# MS1050_EVB_V2_0.net
KiCad netlist of a schematic drawn in Altium Designer
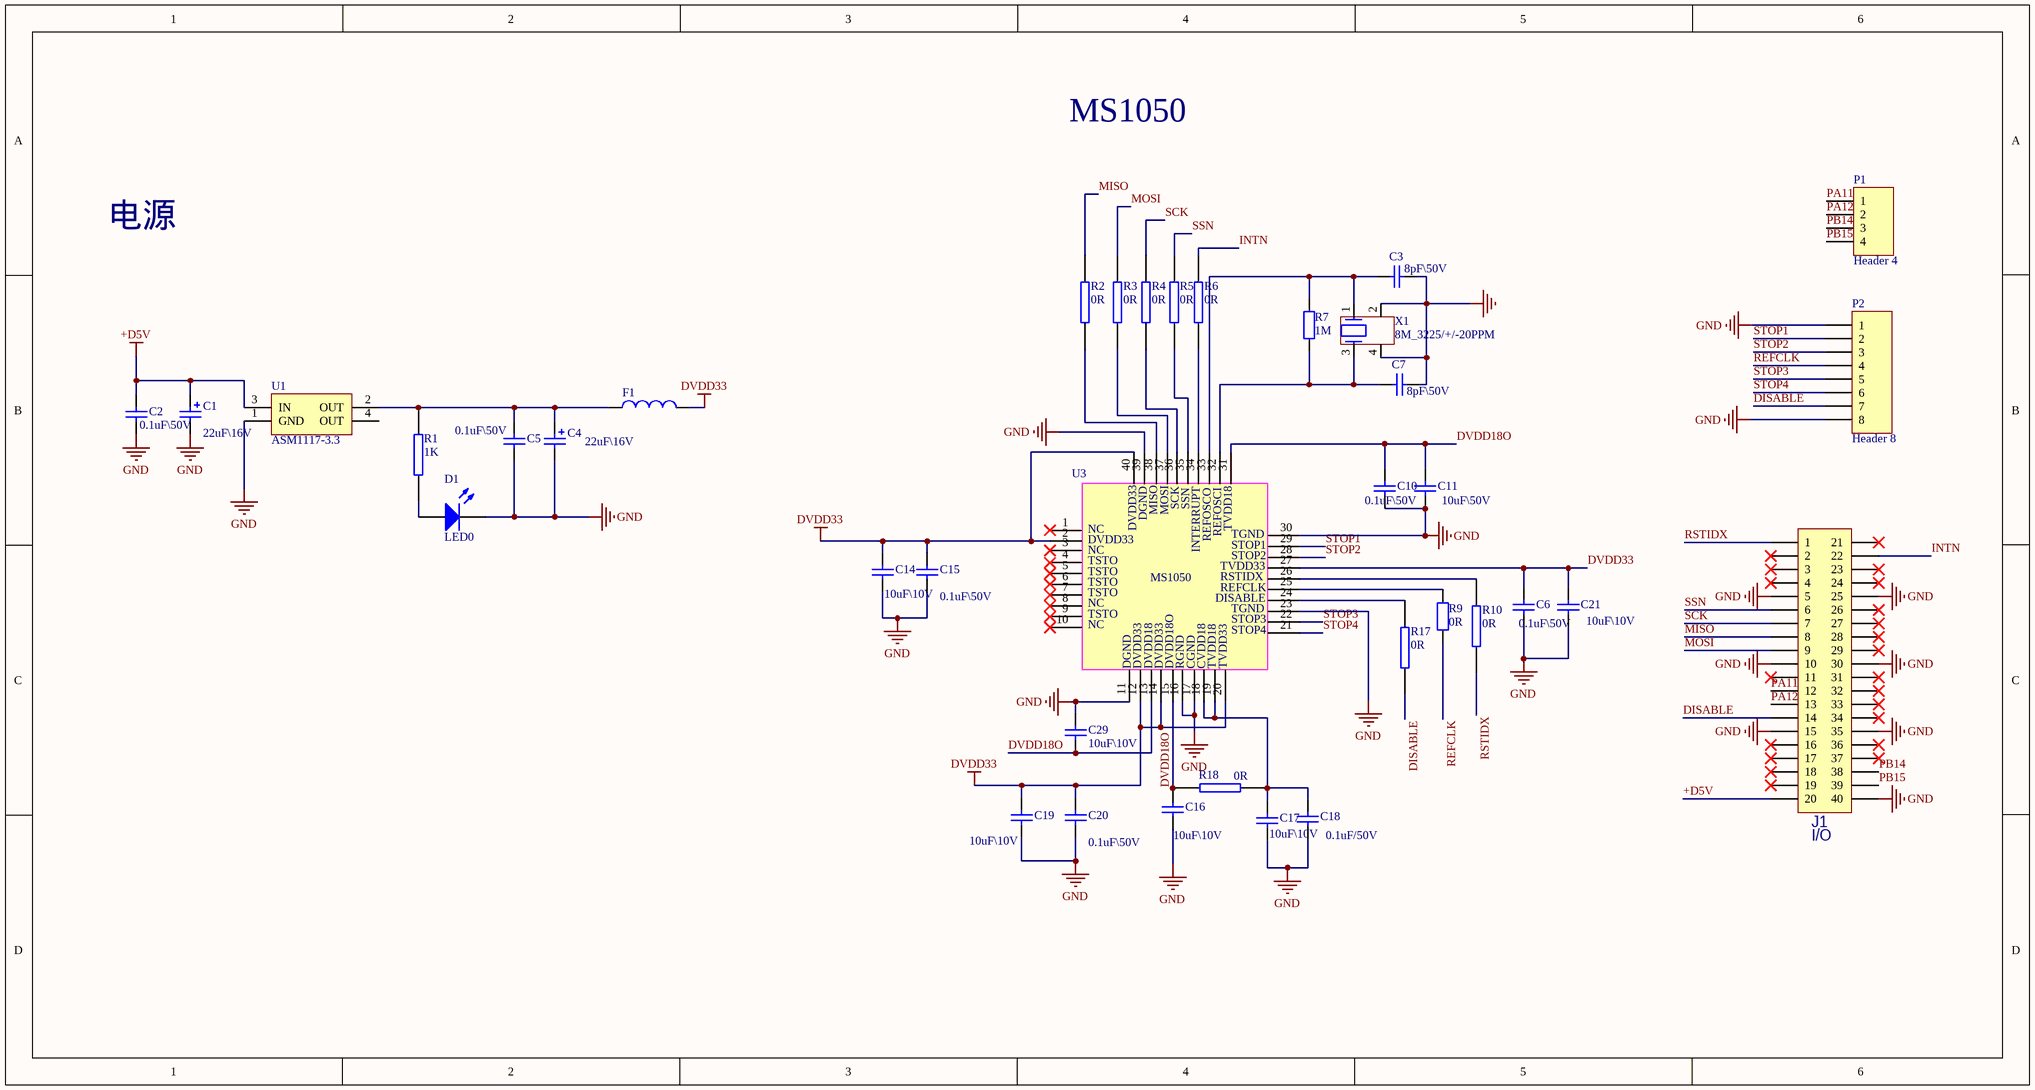
[diagram p0: MS1050_EVB_V2.0.SchDoc]

(export (version "E")
  (design (tool "Eeschema 10.0.6"))
  (components
    (comp (ref "C1")
      (value "22u~{F}16V")
      (footprint "3216")
      (description "Cap，22uF，20%，3216")
      (fields (field (name "Comment") "22uF") (field (name "PUBLISHER") "Altium Limited"))
      (libsource (lib "Miscellaneous Devices") (part "Cap Pol2"))
    )
    (comp (ref "C2")
      (value "0.1u~{F}50V")
      (footprint "0603C")
      (description "Cap，0.1 uF，1%，0603")
      (fields (field (name "Comment") "0.1uF") (field (name "PUBLISHER") "Altium Limited"))
      (libsource (lib "Miscellaneous Devices") (part "Cap"))
    )
    (comp (ref "C3")
      (value "8p~{F}50V")
      (footprint "0603C")
      (description "Cap，8pF，1%，0603")
      (fields (field (name "Comment") "8pF") (field (name "PUBLISHER") "Altium Limited"))
      (libsource (lib "Miscellaneous Devices") (part "Cap"))
    )
    (comp (ref "C4")
      (value "22u~{F}16V")
      (footprint "3216")
      (description "Cap，22uF，20%，3216")
      (fields (field (name "Comment") "22uF") (field (name "PUBLISHER") "Altium Limited"))
      (libsource (lib "Miscellaneous Devices") (part "Cap Pol2"))
    )
    (comp (ref "C5")
      (value "0.1u~{F}50V")
      (footprint "0603c")
      (description "Cap，0.1uF，1%，0603")
      (fields (field (name "Comment") "0.1uF") (field (name "PUBLISHER") "Altium Limited"))
      (libsource (lib "Miscellaneous Devices") (part "Cap"))
    )
    (comp (ref "C6")
      (value "0.1u~{F}50V")
      (footprint "0603c")
      (description "Cap，0.1uF，1%，0603")
      (fields (field (name "Comment") "0.1uF") (field (name "PUBLISHER") "Altium Limited"))
      (libsource (lib "MS1050_Demo") (part "Cap"))
    )
    (comp (ref "C7")
      (value "8p~{F}50V")
      (footprint "0603C")
      (description "Cap，8pF，1%，0603")
      (fields (field (name "Comment") "8pF") (field (name "PUBLISHER") "Altium Limited"))
      (libsource (lib "Miscellaneous Devices") (part "Cap"))
    )
    (comp (ref "C10")
      (value "0.1u~{F}50V")
      (footprint "0603c")
      (description "Cap，0.1uF，1%，0603")
      (fields (field (name "Comment") "0.1uF") (field (name "PUBLISHER") "Altium Limited"))
      (libsource (lib "MS1050_Demo") (part "Cap"))
    )
    (comp (ref "C11")
      (value "10u~{F}50V")
      (footprint "0603c")
      (description "Cap，10 uF，1%，0603")
      (fields (field (name "Comment") "10uF") (field (name "PUBLISHER") "Altium Limited"))
      (libsource (lib "MS1050_Demo") (part "Cap"))
    )
    (comp (ref "C14")
      (value "10u~{F}10V")
      (footprint "0603c")
      (description "Cap，10 uF，1%，0603")
      (fields (field (name "Comment") "10uF") (field (name "PUBLISHER") "Altium Limited"))
      (libsource (lib "MS1050_Demo") (part "Cap"))
    )
    (comp (ref "C15")
      (value "0.1u~{F}50V")
      (footprint "0603c")
      (description "Cap，0.1uF，1%，0603")
      (fields (field (name "Comment") "0.1uF") (field (name "PUBLISHER") "Altium Limited"))
      (libsource (lib "MS1050_Demo") (part "Cap"))
    )
    (comp (ref "C16")
      (value "10u~{F}10V")
      (footprint "0603c")
      (description "Cap，10 uF，1%，0603")
      (fields (field (name "Comment") "10uF") (field (name "PUBLISHER") "Altium Limited"))
      (libsource (lib "MS1050_Demo") (part "Cap"))
    )
    (comp (ref "C17")
      (value "10u~{F}10V")
      (footprint "0603c")
      (description "Cap，10 uF，1%，0603")
      (fields (field (name "Comment") "10uF") (field (name "PUBLISHER") "Altium Limited"))
      (libsource (lib "MS1050_Demo") (part "Cap"))
    )
    (comp (ref "C18")
      (value "0.1uF/50V")
      (footprint "0603c")
      (description "Cap，0.1uF，1%，0603")
      (fields (field (name "Comment") "0.1uF") (field (name "PUBLISHER") "Altium Limited"))
      (libsource (lib "MS1050_Demo") (part "Cap"))
    )
    (comp (ref "C19")
      (value "10u~{F}10V")
      (footprint "0603c")
      (description "Cap，10 uF，1%，0603")
      (fields (field (name "Comment") "10uF") (field (name "PUBLISHER") "Altium Limited"))
      (libsource (lib "MS1050_Demo") (part "Cap"))
    )
    (comp (ref "C20")
      (value "0.1u~{F}50V")
      (footprint "0603c")
      (description "Cap，0.1uF，1%，0603")
      (fields (field (name "Comment") "0.1uF") (field (name "PUBLISHER") "Altium Limited"))
      (libsource (lib "MS1050_Demo") (part "Cap"))
    )
    (comp (ref "C21")
      (value "10u~{F}10V")
      (footprint "0603c")
      (description "Cap，10 uF，1%，0603")
      (fields (field (name "Comment") "10uF") (field (name "PUBLISHER") "Altium Limited"))
      (libsource (lib "MS1050_Demo") (part "Cap"))
    )
    (comp (ref "C29")
      (value "10u~{F}10V")
      (footprint "0603c")
      (description "Cap，10 uF，1%，0603")
      (fields (field (name "Comment") "10uF") (field (name "PUBLISHER") "Altium Limited"))
      (libsource (lib "MS1050_Demo") (part "Cap"))
    )
    (comp (ref "D1")
      (value "LED0")
      (footprint "LED 0603R")
      (description "Green LED")
      (fields (field (name "PUBLISHER") "Altium Limited"))
      (libsource (lib "Miscellaneous Devices") (part "LED0"))
    )
    (comp (ref "F1")
      (value "~")
      (footprint "R0603")
      (description "Inductor")
      (fields (field (name "PUBLISHER") "Altium Limited"))
      (libsource (lib "Miscellaneous Devices") (part "Inductor"))
    )
    (comp (ref "J1")
      (value "I/O")
      (footprint "SIP20x2B")
      (description "Header, 40-Pin, Dual row")
      (fields (field (name "PUBLISHER") "*"))
      (libsource (lib "My_Schlib") (part "Header 20X2A"))
    )
    (comp (ref "P1")
      (value "Header 4")
      (footprint "HDR1X4")
      (description "Header, 4-Pin")
      (fields (field (name "PUBLISHER") "Altium Limited"))
      (libsource (lib "MS1050_Demo") (part "Header 4"))
    )
    (comp (ref "P2")
      (value "Header 8")
      (footprint "HDR1X8")
      (description "Header, 8-Pin")
      (fields (field (name "PUBLISHER") "Altium Limited"))
      (libsource (lib "Miscellaneous Connectors") (part "Header 8"))
    )
    (comp (ref "R1")
      (value "1K")
      (footprint "R0603")
      (description "RES，1.00K ohm，1%，0.125W，0603")
      (libsource (lib "*") (part "RES2"))
    )
    (comp (ref "R2")
      (value "0R")
      (footprint "R0603")
      (description "RES，0 ohm，1%，0.125W，0603")
      (libsource (lib "MS1050_Demo") (part "RES2_1"))
    )
    (comp (ref "R3")
      (value "0R")
      (footprint "R0603")
      (description "RES，0 ohm，1%，0.125W，0603")
      (libsource (lib "MS1050_Demo") (part "RES2_1"))
    )
    (comp (ref "R4")
      (value "0R")
      (footprint "R0603")
      (description "RES，0 ohm，1%，0.125W，0603")
      (libsource (lib "MS1050_Demo") (part "RES2_1"))
    )
    (comp (ref "R5")
      (value "0R")
      (footprint "R0603")
      (description "RES，0 ohm，1%，0.125W，0603")
      (libsource (lib "MS1050_Demo") (part "RES2_1"))
    )
    (comp (ref "R6")
      (value "0R")
      (footprint "R0603")
      (description "RES，0 ohm，1%，0.125W，0603")
      (libsource (lib "MS1050_Demo") (part "RES2_1"))
    )
    (comp (ref "R7")
      (value "1M")
      (footprint "R0603")
      (description "RES，1M ohm，1%，0.125W，0603")
      (fields (field (name "PUBLISHER") "Altium Limited"))
      (libsource (lib "Miscellaneous Devices") (part "Res2"))
    )
    (comp (ref "R9")
      (value "0R")
      (footprint "R0603")
      (description "Resistor")
      (fields (field (name "Comment") "Res2") (field (name "PUBLISHER") "Altium Limited"))
      (libsource (lib "MS1050_Demo") (part "Res2_3"))
    )
    (comp (ref "R10")
      (value "0R")
      (footprint "R0603")
      (description "RES，0 ohm，1%，0.125W，0603")
      (libsource (lib "MS1050_Demo") (part "RES2_1"))
    )
    (comp (ref "R17")
      (value "0R")
      (footprint "R0603")
      (description "RES，0 ohm，1%，0.125W，0603")
      (libsource (lib "MS1050_Demo") (part "RES2_1"))
    )
    (comp (ref "R18")
      (value "0R")
      (footprint "R0603")
      (description "RES，0 ohm，1%，0.125W，0603")
      (libsource (lib "MS1050_Demo") (part "RES2_1"))
    )
    (comp (ref "U1")
      (value "ASM1117-3.3")
      (footprint "1117")
      (description "800mA and 1A Low Dropout Positive Regulator 2.85V, 3.3V, 5V, and Adjustable")
      (fields (field (name "PUBLISHER") "Altium Limited"))
      (libsource (lib "*") (part "REG1117-3.3"))
    )
    (comp (ref "U3")
      (value "MS1050")
      (footprint "QFN40 6X6_L")
      (libsource (lib "MS1050_Demo") (part "MS1050"))
    )
    (comp (ref "X1")
      (value "8M_3225/+/-20PPM")
      (footprint "OSC 4025-4P")
      (description "SMD3225, 8MHz, 12pF 10%")
      (fields (field (name "MANUFACTURER") "SJK") (field (name "PARTNUMBER") "7U08000E12UCG"))
      (libsource (lib "schlib") (part "XTAL_4_PINS"))
    )
  )
  (nets
    (net (code "1") (name "+D5V") (class "Default")
      (node (ref "C1") (pin "1") (pinfunction "1_1") (pintype "passive"))
      (node (ref "C2") (pin "2") (pinfunction "2_2") (pintype "passive"))
      (node (ref "J1") (pin "20") (pinfunction "20_20") (pintype "passive"))
      (node (ref "U1") (pin "3") (pinfunction "IN_3") (pintype "power_in"))
    )
    (net (code "2") (name "/DISABLE") (class "Default")
      (node (ref "J1") (pin "14") (pinfunction "14_14") (pintype "passive"))
      (node (ref "P2") (pin "7") (pinfunction "7_7") (pintype "passive"))
      (node (ref "R17") (pin "2") (pinfunction "2_2") (pintype "passive"))
    )
    (net (code "3") (name "/DVDD18O") (class "Default")
      (node (ref "C10") (pin "2") (pinfunction "2_2") (pintype "passive"))
      (node (ref "C11") (pin "1") (pinfunction "1_1") (pintype "passive"))
      (node (ref "C16") (pin "2") (pinfunction "2_2") (pintype "passive"))
      (node (ref "C29") (pin "1") (pinfunction "1_1") (pintype "passive"))
      (node (ref "R18") (pin "1") (pinfunction "1_1") (pintype "passive"))
      (node (ref "U3") (pin "13") (pinfunction "13_13") (pintype "passive"))
      (node (ref "U3") (pin "15") (pinfunction "15_15") (pintype "passive"))
      (node (ref "U3") (pin "31") (pinfunction "31_31") (pintype "passive"))
    )
    (net (code "4") (name "/INTN") (class "Default")
      (node (ref "J1") (pin "22") (pinfunction "22_22") (pintype "passive"))
      (node (ref "R6") (pin "2") (pinfunction "2_2") (pintype "passive"))
    )
    (net (code "5") (name "/MISO") (class "Default")
      (node (ref "J1") (pin "8") (pinfunction "8_8") (pintype "passive"))
      (node (ref "R2") (pin "2") (pinfunction "2_2") (pintype "passive"))
    )
    (net (code "6") (name "/MOSI") (class "Default")
      (node (ref "J1") (pin "9") (pinfunction "9_9") (pintype "passive"))
      (node (ref "R3") (pin "2") (pinfunction "2_2") (pintype "passive"))
    )
    (net (code "7") (name "/PA11") (class "Default")
      (node (ref "J1") (pin "12") (pinfunction "12_12") (pintype "passive"))
      (node (ref "P1") (pin "1") (pinfunction "1_1") (pintype "passive"))
    )
    (net (code "8") (name "/PA12") (class "Default")
      (node (ref "J1") (pin "13") (pinfunction "13_13") (pintype "passive"))
      (node (ref "P1") (pin "2") (pinfunction "2_2") (pintype "passive"))
    )
    (net (code "9") (name "/PB14") (class "Default")
      (node (ref "J1") (pin "38") (pinfunction "38_38") (pintype "passive"))
      (node (ref "P1") (pin "3") (pinfunction "3_3") (pintype "passive"))
    )
    (net (code "10") (name "/PB15") (class "Default")
      (node (ref "J1") (pin "39") (pinfunction "39_39") (pintype "passive"))
      (node (ref "P1") (pin "4") (pinfunction "4_4") (pintype "passive"))
    )
    (net (code "11") (name "/REFCLK") (class "Default")
      (node (ref "P2") (pin "4") (pinfunction "4_4") (pintype "passive"))
      (node (ref "R9") (pin "1") (pinfunction "1_1") (pintype "passive"))
    )
    (net (code "12") (name "/RSTIDX") (class "Default")
      (node (ref "J1") (pin "1") (pinfunction "1_1") (pintype "passive"))
      (node (ref "R10") (pin "2") (pinfunction "2_2") (pintype "passive"))
    )
    (net (code "13") (name "/SCK") (class "Default")
      (node (ref "J1") (pin "7") (pinfunction "7_7") (pintype "passive"))
      (node (ref "R4") (pin "2") (pinfunction "2_2") (pintype "passive"))
    )
    (net (code "14") (name "/SSN") (class "Default")
      (node (ref "J1") (pin "6") (pinfunction "6_6") (pintype "passive"))
      (node (ref "R5") (pin "2") (pinfunction "2_2") (pintype "passive"))
    )
    (net (code "15") (name "/STOP1") (class "Default")
      (node (ref "P2") (pin "2") (pinfunction "2_2") (pintype "passive"))
      (node (ref "U3") (pin "29") (pinfunction "29_29") (pintype "passive"))
    )
    (net (code "16") (name "/STOP2") (class "Default")
      (node (ref "P2") (pin "3") (pinfunction "3_3") (pintype "passive"))
      (node (ref "U3") (pin "28") (pinfunction "28_28") (pintype "passive"))
    )
    (net (code "17") (name "/STOP3") (class "Default")
      (node (ref "P2") (pin "5") (pinfunction "5_5") (pintype "passive"))
      (node (ref "U3") (pin "22") (pinfunction "22_22") (pintype "passive"))
    )
    (net (code "18") (name "/STOP4") (class "Default")
      (node (ref "P2") (pin "6") (pinfunction "6_6") (pintype "passive"))
      (node (ref "U3") (pin "21") (pinfunction "21_21") (pintype "passive"))
    )
    (net (code "19") (name "DVDD33") (class "Default")
      (node (ref "C14") (pin "2") (pinfunction "2_2") (pintype "passive"))
      (node (ref "C15") (pin "2") (pinfunction "2_2") (pintype "passive"))
      (node (ref "C19") (pin "2") (pinfunction "2_2") (pintype "passive"))
      (node (ref "C20") (pin "2") (pinfunction "2_2") (pintype "passive"))
      (node (ref "C21") (pin "1") (pinfunction "1_1") (pintype "passive"))
      (node (ref "C6") (pin "1") (pinfunction "1_1") (pintype "passive"))
      (node (ref "F1") (pin "2") (pinfunction "2_2") (pintype "passive"))
      (node (ref "U3") (pin "12") (pinfunction "12_12") (pintype "passive"))
      (node (ref "U3") (pin "14") (pinfunction "14_14") (pintype "passive"))
      (node (ref "U3") (pin "2") (pinfunction "2_2") (pintype "passive"))
      (node (ref "U3") (pin "20") (pinfunction "20_20") (pintype "passive"))
      (node (ref "U3") (pin "27") (pinfunction "27_27") (pintype "passive"))
      (node (ref "U3") (pin "40") (pinfunction "40_40") (pintype "passive"))
    )
    (net (code "20") (name "GND") (class "Default")
      (node (ref "C1") (pin "2") (pinfunction "2_2") (pintype "passive"))
      (node (ref "C10") (pin "1") (pinfunction "1_1") (pintype "passive"))
      (node (ref "C11") (pin "2") (pinfunction "2_2") (pintype "passive"))
      (node (ref "C14") (pin "1") (pinfunction "1_1") (pintype "passive"))
      (node (ref "C15") (pin "1") (pinfunction "1_1") (pintype "passive"))
      (node (ref "C16") (pin "1") (pinfunction "1_1") (pintype "passive"))
      (node (ref "C17") (pin "1") (pinfunction "1_1") (pintype "passive"))
      (node (ref "C18") (pin "1") (pinfunction "1_1") (pintype "passive"))
      (node (ref "C19") (pin "1") (pinfunction "1_1") (pintype "passive"))
      (node (ref "C2") (pin "1") (pinfunction "1_1") (pintype "passive"))
      (node (ref "C20") (pin "1") (pinfunction "1_1") (pintype "passive"))
      (node (ref "C21") (pin "2") (pinfunction "2_2") (pintype "passive"))
      (node (ref "C29") (pin "2") (pinfunction "2_2") (pintype "passive"))
      (node (ref "C3") (pin "2") (pinfunction "2_2") (pintype "passive"))
      (node (ref "C4") (pin "2") (pinfunction "2_2") (pintype "passive"))
      (node (ref "C5") (pin "1") (pinfunction "1_1") (pintype "passive"))
      (node (ref "C6") (pin "2") (pinfunction "2_2") (pintype "passive"))
      (node (ref "C7") (pin "2") (pinfunction "2_2") (pintype "passive"))
      (node (ref "D1") (pin "2") (pinfunction "K_2") (pintype "passive"))
      (node (ref "J1") (pin "10") (pinfunction "10_10") (pintype "passive"))
      (node (ref "J1") (pin "15") (pinfunction "15_15") (pintype "passive"))
      (node (ref "J1") (pin "25") (pinfunction "25_25") (pintype "passive"))
      (node (ref "J1") (pin "30") (pinfunction "30_30") (pintype "passive"))
      (node (ref "J1") (pin "35") (pinfunction "35_35") (pintype "passive"))
      (node (ref "J1") (pin "40") (pinfunction "40_40") (pintype "passive"))
      (node (ref "J1") (pin "5") (pinfunction "5_5") (pintype "passive"))
      (node (ref "P2") (pin "1") (pinfunction "1_1") (pintype "passive"))
      (node (ref "P2") (pin "8") (pinfunction "8_8") (pintype "passive"))
      (node (ref "U1") (pin "1") (pinfunction "GND_1") (pintype "power_in"))
      (node (ref "U3") (pin "11") (pinfunction "11_11") (pintype "passive"))
      (node (ref "U3") (pin "16") (pinfunction "16_16") (pintype "passive"))
      (node (ref "U3") (pin "17") (pinfunction "17_17") (pintype "passive"))
      (node (ref "U3") (pin "23") (pinfunction "23_23") (pintype "passive"))
      (node (ref "U3") (pin "30") (pinfunction "30_30") (pintype "passive"))
      (node (ref "U3") (pin "39") (pinfunction "39_39") (pintype "passive"))
      (node (ref "X1") (pin "2") (pinfunction "2_2") (pintype "passive"))
      (node (ref "X1") (pin "4") (pinfunction "4_4") (pintype "passive"))
    )
    (net (code "21") (name "Net-(C3-Pad1)") (class "Default")
      (node (ref "C3") (pin "1") (pinfunction "1_1") (pintype "passive"))
      (node (ref "R7") (pin "1") (pinfunction "1_1") (pintype "passive"))
      (node (ref "U3") (pin "33") (pinfunction "33_33") (pintype "passive"))
      (node (ref "X1") (pin "1") (pinfunction "1_1") (pintype "passive"))
    )
    (net (code "22") (name "Net-(C4-Pad1)") (class "Default")
      (node (ref "C4") (pin "1") (pinfunction "1_1") (pintype "passive"))
      (node (ref "C5") (pin "2") (pinfunction "2_2") (pintype "passive"))
      (node (ref "F1") (pin "1") (pinfunction "1_1") (pintype "passive"))
      (node (ref "R1") (pin "1") (pinfunction "1_1") (pintype "passive"))
      (node (ref "U1") (pin "2") (pinfunction "OUT_2") (pintype "power_in"))
    )
    (net (code "23") (name "Net-(C7-Pad1)") (class "Default")
      (node (ref "C7") (pin "1") (pinfunction "1_1") (pintype "passive"))
      (node (ref "R7") (pin "2") (pinfunction "2_2") (pintype "passive"))
      (node (ref "U3") (pin "32") (pinfunction "32_32") (pintype "passive"))
      (node (ref "X1") (pin "3") (pinfunction "3_3") (pintype "passive"))
    )
    (net (code "24") (name "Net-(C17-Pad2)") (class "Default")
      (node (ref "C17") (pin "2") (pinfunction "2_2") (pintype "passive"))
      (node (ref "C18") (pin "2") (pinfunction "2_2") (pintype "passive"))
      (node (ref "R18") (pin "2") (pinfunction "2_2") (pintype "passive"))
      (node (ref "U3") (pin "18") (pinfunction "18_18") (pintype "passive"))
      (node (ref "U3") (pin "19") (pinfunction "19_19") (pintype "passive"))
    )
    (net (code "25") (name "Net-(D1-A)") (class "Default")
      (node (ref "D1") (pin "1") (pinfunction "A_1") (pintype "passive"))
      (node (ref "R1") (pin "2") (pinfunction "2_2") (pintype "passive"))
    )
    (net (code "26") (name "Net-(R2-Pad1)") (class "Default")
      (node (ref "R2") (pin "1") (pinfunction "1_1") (pintype "passive"))
      (node (ref "U3") (pin "38") (pinfunction "38_38") (pintype "passive"))
    )
    (net (code "27") (name "Net-(R3-Pad1)") (class "Default")
      (node (ref "R3") (pin "1") (pinfunction "1_1") (pintype "passive"))
      (node (ref "U3") (pin "37") (pinfunction "37_37") (pintype "passive"))
    )
    (net (code "28") (name "Net-(R4-Pad1)") (class "Default")
      (node (ref "R4") (pin "1") (pinfunction "1_1") (pintype "passive"))
      (node (ref "U3") (pin "36") (pinfunction "36_36") (pintype "passive"))
    )
    (net (code "29") (name "Net-(R5-Pad1)") (class "Default")
      (node (ref "R5") (pin "1") (pinfunction "1_1") (pintype "passive"))
      (node (ref "U3") (pin "35") (pinfunction "35_35") (pintype "passive"))
    )
    (net (code "30") (name "Net-(R6-Pad1)") (class "Default")
      (node (ref "R6") (pin "1") (pinfunction "1_1") (pintype "passive"))
      (node (ref "U3") (pin "34") (pinfunction "34_34") (pintype "passive"))
    )
    (net (code "31") (name "Net-(R9-Pad2)") (class "Default")
      (node (ref "R9") (pin "2") (pinfunction "2_2") (pintype "passive"))
      (node (ref "U3") (pin "25") (pinfunction "25_25") (pintype "passive"))
    )
    (net (code "32") (name "Net-(R10-Pad1)") (class "Default")
      (node (ref "R10") (pin "1") (pinfunction "1_1") (pintype "passive"))
      (node (ref "U3") (pin "26") (pinfunction "26_26") (pintype "passive"))
    )
    (net (code "33") (name "Net-(R17-Pad1)") (class "Default")
      (node (ref "R17") (pin "1") (pinfunction "1_1") (pintype "passive"))
      (node (ref "U3") (pin "24") (pinfunction "24_24") (pintype "passive"))
    )
    (net (code "34") (name "unconnected-(J1-Pad2)") (class "Default")
      (node (ref "J1") (pin "2") (pinfunction "2_2") (pintype "passive+no_connect"))
    )
    (net (code "35") (name "unconnected-(J1-Pad3)") (class "Default")
      (node (ref "J1") (pin "3") (pinfunction "3_3") (pintype "passive+no_connect"))
    )
    (net (code "36") (name "unconnected-(J1-Pad4)") (class "Default")
      (node (ref "J1") (pin "4") (pinfunction "4_4") (pintype "passive+no_connect"))
    )
    (net (code "37") (name "unconnected-(J1-Pad11)") (class "Default")
      (node (ref "J1") (pin "11") (pinfunction "11_11") (pintype "passive+no_connect"))
    )
    (net (code "38") (name "unconnected-(J1-Pad16)") (class "Default")
      (node (ref "J1") (pin "16") (pinfunction "16_16") (pintype "passive+no_connect"))
    )
    (net (code "39") (name "unconnected-(J1-Pad17)") (class "Default")
      (node (ref "J1") (pin "17") (pinfunction "17_17") (pintype "passive+no_connect"))
    )
    (net (code "40") (name "unconnected-(J1-Pad18)") (class "Default")
      (node (ref "J1") (pin "18") (pinfunction "18_18") (pintype "passive+no_connect"))
    )
    (net (code "41") (name "unconnected-(J1-Pad19)") (class "Default")
      (node (ref "J1") (pin "19") (pinfunction "19_19") (pintype "passive+no_connect"))
    )
    (net (code "42") (name "unconnected-(J1-Pad21)") (class "Default")
      (node (ref "J1") (pin "21") (pinfunction "21_21") (pintype "passive+no_connect"))
    )
    (net (code "43") (name "unconnected-(J1-Pad23)") (class "Default")
      (node (ref "J1") (pin "23") (pinfunction "23_23") (pintype "passive+no_connect"))
    )
    (net (code "44") (name "unconnected-(J1-Pad24)") (class "Default")
      (node (ref "J1") (pin "24") (pinfunction "24_24") (pintype "passive+no_connect"))
    )
    (net (code "45") (name "unconnected-(J1-Pad26)") (class "Default")
      (node (ref "J1") (pin "26") (pinfunction "26_26") (pintype "passive+no_connect"))
    )
    (net (code "46") (name "unconnected-(J1-Pad27)") (class "Default")
      (node (ref "J1") (pin "27") (pinfunction "27_27") (pintype "passive+no_connect"))
    )
    (net (code "47") (name "unconnected-(J1-Pad28)") (class "Default")
      (node (ref "J1") (pin "28") (pinfunction "28_28") (pintype "passive+no_connect"))
    )
    (net (code "48") (name "unconnected-(J1-Pad29)") (class "Default")
      (node (ref "J1") (pin "29") (pinfunction "29_29") (pintype "passive+no_connect"))
    )
    (net (code "49") (name "unconnected-(J1-Pad31)") (class "Default")
      (node (ref "J1") (pin "31") (pinfunction "31_31") (pintype "passive+no_connect"))
    )
    (net (code "50") (name "unconnected-(J1-Pad32)") (class "Default")
      (node (ref "J1") (pin "32") (pinfunction "32_32") (pintype "passive+no_connect"))
    )
    (net (code "51") (name "unconnected-(J1-Pad33)") (class "Default")
      (node (ref "J1") (pin "33") (pinfunction "33_33") (pintype "passive+no_connect"))
    )
    (net (code "52") (name "unconnected-(J1-Pad34)") (class "Default")
      (node (ref "J1") (pin "34") (pinfunction "34_34") (pintype "passive+no_connect"))
    )
    (net (code "53") (name "unconnected-(J1-Pad36)") (class "Default")
      (node (ref "J1") (pin "36") (pinfunction "36_36") (pintype "passive+no_connect"))
    )
    (net (code "54") (name "unconnected-(J1-Pad37)") (class "Default")
      (node (ref "J1") (pin "37") (pinfunction "37_37") (pintype "passive+no_connect"))
    )
    (net (code "55") (name "unconnected-(U1-OUT-Pad4)") (class "Default")
      (node (ref "U1") (pin "4") (pinfunction "OUT_4") (pintype "power_in"))
    )
    (net (code "56") (name "unconnected-(U3-Pad1)") (class "Default")
      (node (ref "U3") (pin "1") (pinfunction "1_1") (pintype "passive+no_connect"))
    )
    (net (code "57") (name "unconnected-(U3-Pad3)") (class "Default")
      (node (ref "U3") (pin "3") (pinfunction "3_3") (pintype "passive+no_connect"))
    )
    (net (code "58") (name "unconnected-(U3-Pad4)") (class "Default")
      (node (ref "U3") (pin "4") (pinfunction "4_4") (pintype "passive+no_connect"))
    )
    (net (code "59") (name "unconnected-(U3-Pad5)") (class "Default")
      (node (ref "U3") (pin "5") (pinfunction "5_5") (pintype "passive+no_connect"))
    )
    (net (code "60") (name "unconnected-(U3-Pad6)") (class "Default")
      (node (ref "U3") (pin "6") (pinfunction "6_6") (pintype "passive+no_connect"))
    )
    (net (code "61") (name "unconnected-(U3-Pad7)") (class "Default")
      (node (ref "U3") (pin "7") (pinfunction "7_7") (pintype "passive+no_connect"))
    )
    (net (code "62") (name "unconnected-(U3-Pad8)") (class "Default")
      (node (ref "U3") (pin "8") (pinfunction "8_8") (pintype "passive+no_connect"))
    )
    (net (code "63") (name "unconnected-(U3-Pad9)") (class "Default")
      (node (ref "U3") (pin "9") (pinfunction "9_9") (pintype "passive+no_connect"))
    )
    (net (code "64") (name "unconnected-(U3-Pad10)") (class "Default")
      (node (ref "U3") (pin "10") (pinfunction "10_10") (pintype "passive+no_connect"))
    )
  )
)
